# djb_v2_jig.net
KiCad netlist of a schematic drawn in Altium Designer
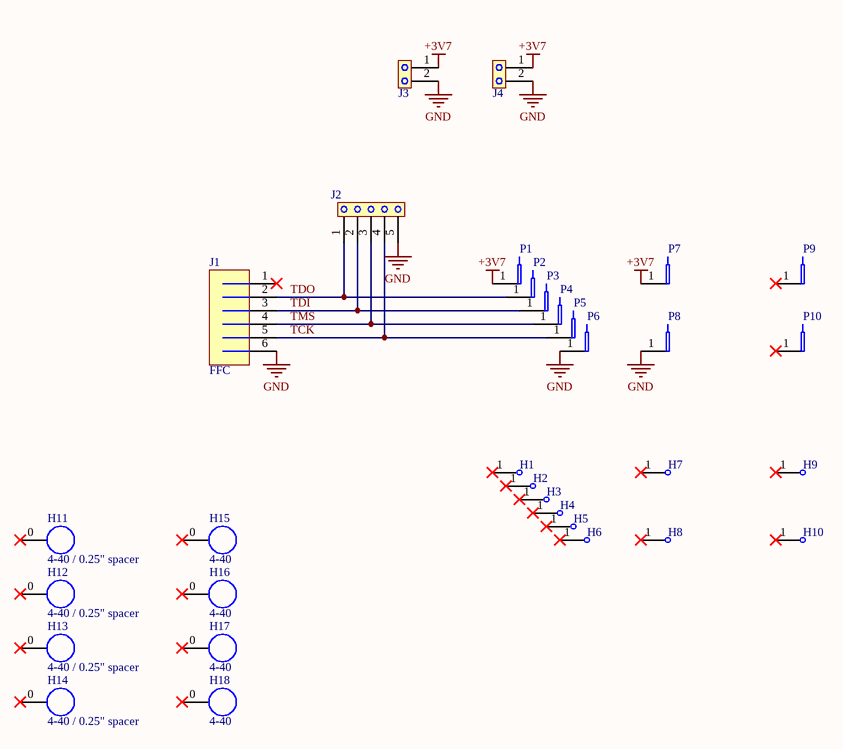
[diagram p0: djb_v2_jig.SchDoc]

(export (version "E")
  (design (tool "Eeschema 10.0.6"))
  (components
    (comp (ref "H1")
      (value "SMITHS_S-00-U-1.3-G_MID")
      (footprint "SMITHS_S-00-U-1.3-G_MID")
      (description "Smiths Interconnect / IDI S-00-U-1.3-G Pogo Pin 0.99mm Centers 16.7mm Long 2.8mm Travel, Mid Mount")
      (libsource (lib "OSP_Symbols") (part "SMITHS_S-00-U-1.3-G_MID"))
    )
    (comp (ref "H2")
      (value "SMITHS_S-00-U-1.3-G_MID")
      (footprint "SMITHS_S-00-U-1.3-G_MID")
      (description "Smiths Interconnect / IDI S-00-U-1.3-G Pogo Pin 0.99mm Centers 16.7mm Long 2.8mm Travel, Mid Mount")
      (libsource (lib "OSP_Symbols") (part "SMITHS_S-00-U-1.3-G_MID"))
    )
    (comp (ref "H3")
      (value "SMITHS_S-00-U-1.3-G_MID")
      (footprint "SMITHS_S-00-U-1.3-G_MID")
      (description "Smiths Interconnect / IDI S-00-U-1.3-G Pogo Pin 0.99mm Centers 16.7mm Long 2.8mm Travel, Mid Mount")
      (libsource (lib "OSP_Symbols") (part "SMITHS_S-00-U-1.3-G_MID"))
    )
    (comp (ref "H4")
      (value "SMITHS_S-00-U-1.3-G_MID")
      (footprint "SMITHS_S-00-U-1.3-G_MID")
      (description "Smiths Interconnect / IDI S-00-U-1.3-G Pogo Pin 0.99mm Centers 16.7mm Long 2.8mm Travel, Mid Mount")
      (libsource (lib "OSP_Symbols") (part "SMITHS_S-00-U-1.3-G_MID"))
    )
    (comp (ref "H5")
      (value "SMITHS_S-00-U-1.3-G_MID")
      (footprint "SMITHS_S-00-U-1.3-G_MID")
      (description "Smiths Interconnect / IDI S-00-U-1.3-G Pogo Pin 0.99mm Centers 16.7mm Long 2.8mm Travel, Mid Mount")
      (libsource (lib "OSP_Symbols") (part "SMITHS_S-00-U-1.3-G_MID"))
    )
    (comp (ref "H6")
      (value "SMITHS_S-00-U-1.3-G_MID")
      (footprint "SMITHS_S-00-U-1.3-G_MID")
      (description "Smiths Interconnect / IDI S-00-U-1.3-G Pogo Pin 0.99mm Centers 16.7mm Long 2.8mm Travel, Mid Mount")
      (libsource (lib "OSP_Symbols") (part "SMITHS_S-00-U-1.3-G_MID"))
    )
    (comp (ref "H7")
      (value "SMITHS_S-00-U-1.3-G_MID")
      (footprint "SMITHS_S-00-U-1.3-G_MID")
      (description "Smiths Interconnect / IDI S-00-U-1.3-G Pogo Pin 0.99mm Centers 16.7mm Long 2.8mm Travel, Mid Mount")
      (libsource (lib "OSP_Symbols") (part "SMITHS_S-00-U-1.3-G_MID"))
    )
    (comp (ref "H8")
      (value "SMITHS_S-00-U-1.3-G_MID")
      (footprint "SMITHS_S-00-U-1.3-G_MID")
      (description "Smiths Interconnect / IDI S-00-U-1.3-G Pogo Pin 0.99mm Centers 16.7mm Long 2.8mm Travel, Mid Mount")
      (libsource (lib "OSP_Symbols") (part "SMITHS_S-00-U-1.3-G_MID"))
    )
    (comp (ref "H9")
      (value "SMITHS_S-00-U-1.3-G_MID")
      (footprint "SMITHS_S-00-U-1.3-G_MID")
      (description "Smiths Interconnect / IDI S-00-U-1.3-G Pogo Pin 0.99mm Centers 16.7mm Long 2.8mm Travel, Mid Mount")
      (libsource (lib "OSP_Symbols") (part "SMITHS_S-00-U-1.3-G_MID"))
    )
    (comp (ref "H10")
      (value "SMITHS_S-00-U-1.3-G_MID")
      (footprint "SMITHS_S-00-U-1.3-G_MID")
      (description "Smiths Interconnect / IDI S-00-U-1.3-G Pogo Pin 0.99mm Centers 16.7mm Long 2.8mm Travel, Mid Mount")
      (libsource (lib "OSP_Symbols") (part "SMITHS_S-00-U-1.3-G_MID"))
    )
    (comp (ref "H11")
      (value "4-40 / 0.25\" spacer")
      (footprint "SCREW_4-40_1/4-SPACER")
      (libsource (lib "OSP_Symbols") (part "SCREW_4-40_1/4-SPACER"))
    )
    (comp (ref "H12")
      (value "4-40 / 0.25\" spacer")
      (footprint "SCREW_4-40_1/4-SPACER")
      (libsource (lib "OSP_Symbols") (part "SCREW_4-40_1/4-SPACER"))
    )
    (comp (ref "H13")
      (value "4-40 / 0.25\" spacer")
      (footprint "SCREW_4-40_1/4-SPACER")
      (libsource (lib "OSP_Symbols") (part "SCREW_4-40_1/4-SPACER"))
    )
    (comp (ref "H14")
      (value "4-40 / 0.25\" spacer")
      (footprint "SCREW_4-40_1/4-SPACER")
      (libsource (lib "OSP_Symbols") (part "SCREW_4-40_1/4-SPACER"))
    )
    (comp (ref "H15")
      (value "4-40")
      (footprint "SCREW_4-40_BLANK")
      (libsource (lib "OSP_Symbols") (part "SCREW_4-40_EMPTY"))
    )
    (comp (ref "H16")
      (value "4-40")
      (footprint "SCREW_4-40_BLANK")
      (libsource (lib "OSP_Symbols") (part "SCREW_4-40_EMPTY"))
    )
    (comp (ref "H17")
      (value "4-40")
      (footprint "SCREW_4-40_BLANK")
      (libsource (lib "OSP_Symbols") (part "SCREW_4-40_EMPTY"))
    )
    (comp (ref "H18")
      (value "4-40")
      (footprint "SCREW_4-40_BLANK")
      (libsource (lib "OSP_Symbols") (part "SCREW_4-40_EMPTY"))
    )
    (comp (ref "J1")
      (value "FFC")
      (footprint "AMPHENOL_HFW6R-1STE1LF")
      (description "Amphenol HFW6R-1STE1LF 6-pin flat flexible cable connector")
      (libsource (lib "OSP_Symbols") (part "AMPHENOL_HFW6R-1STE1LF"))
    )
    (comp (ref "J2")
      (value "HDR_5")
      (footprint "HDR_5")
      (description "5-pin 0.1\" header")
      (libsource (lib "OSP_Symbols") (part "HDR_5"))
    )
    (comp (ref "J3")
      (value "HDR_2")
      (footprint "HDR_2")
      (description "2-pin 0.1\" header")
      (libsource (lib "OSP_Symbols") (part "HDR_2"))
    )
    (comp (ref "J4")
      (value "HDR_2")
      (footprint "HDR_2")
      (description "2-pin 0.1\" header")
      (libsource (lib "OSP_Symbols") (part "HDR_2"))
    )
    (comp (ref "P1")
      (value "SMITHS_S-00-U-1.3-G_TH")
      (footprint "SMITHS_S-00-U-1.3-G_TH")
      (libsource (lib "OSP_Symbols") (part "SMITHS_S-00-U-1.3-G_TH"))
    )
    (comp (ref "P2")
      (value "SMITHS_S-00-U-1.3-G_TH")
      (footprint "SMITHS_S-00-U-1.3-G_TH")
      (libsource (lib "OSP_Symbols") (part "SMITHS_S-00-U-1.3-G_TH"))
    )
    (comp (ref "P3")
      (value "SMITHS_S-00-U-1.3-G_TH")
      (footprint "SMITHS_S-00-U-1.3-G_TH")
      (libsource (lib "OSP_Symbols") (part "SMITHS_S-00-U-1.3-G_TH"))
    )
    (comp (ref "P4")
      (value "SMITHS_S-00-U-1.3-G_TH")
      (footprint "SMITHS_S-00-U-1.3-G_TH")
      (libsource (lib "OSP_Symbols") (part "SMITHS_S-00-U-1.3-G_TH"))
    )
    (comp (ref "P5")
      (value "SMITHS_S-00-U-1.3-G_TH")
      (footprint "SMITHS_S-00-U-1.3-G_TH")
      (libsource (lib "OSP_Symbols") (part "SMITHS_S-00-U-1.3-G_TH"))
    )
    (comp (ref "P6")
      (value "SMITHS_S-00-U-1.3-G_TH")
      (footprint "SMITHS_S-00-U-1.3-G_TH")
      (libsource (lib "OSP_Symbols") (part "SMITHS_S-00-U-1.3-G_TH"))
    )
    (comp (ref "P7")
      (value "SMITHS_S-00-U-1.3-G_TH")
      (footprint "SMITHS_S-00-U-1.3-G_TH")
      (libsource (lib "OSP_Symbols") (part "SMITHS_S-00-U-1.3-G_TH"))
    )
    (comp (ref "P8")
      (value "SMITHS_S-00-U-1.3-G_TH")
      (footprint "SMITHS_S-00-U-1.3-G_TH")
      (libsource (lib "OSP_Symbols") (part "SMITHS_S-00-U-1.3-G_TH"))
    )
    (comp (ref "P9")
      (value "SMITHS_S-00-U-1.3-G_TH")
      (footprint "SMITHS_S-00-U-1.3-G_TH")
      (libsource (lib "OSP_Symbols") (part "SMITHS_S-00-U-1.3-G_TH"))
    )
    (comp (ref "P10")
      (value "SMITHS_S-00-U-1.3-G_TH")
      (footprint "SMITHS_S-00-U-1.3-G_TH")
      (libsource (lib "OSP_Symbols") (part "SMITHS_S-00-U-1.3-G_TH"))
    )
  )
  (nets
    (net (code "1") (name "+3V7") (class "Default")
      (node (ref "J3") (pin "1") (pintype "passive"))
      (node (ref "J4") (pin "1") (pintype "passive"))
      (node (ref "P1") (pin "1") (pinfunction "1_1") (pintype "passive"))
      (node (ref "P7") (pin "1") (pinfunction "1_1") (pintype "passive"))
    )
    (net (code "2") (name "/TCK") (class "Default")
      (node (ref "J1") (pin "5") (pintype "passive"))
      (node (ref "J2") (pin "4") (pintype "passive"))
      (node (ref "P5") (pin "1") (pinfunction "1_1") (pintype "passive"))
    )
    (net (code "3") (name "/TDI") (class "Default")
      (node (ref "J1") (pin "3") (pintype "passive"))
      (node (ref "J2") (pin "2") (pintype "passive"))
      (node (ref "P3") (pin "1") (pinfunction "1_1") (pintype "passive"))
    )
    (net (code "4") (name "/TDO") (class "Default")
      (node (ref "J1") (pin "2") (pintype "passive"))
      (node (ref "J2") (pin "1") (pintype "passive"))
      (node (ref "P2") (pin "1") (pinfunction "1_1") (pintype "passive"))
    )
    (net (code "5") (name "/TMS") (class "Default")
      (node (ref "J1") (pin "4") (pintype "passive"))
      (node (ref "J2") (pin "3") (pintype "passive"))
      (node (ref "P4") (pin "1") (pinfunction "1_1") (pintype "passive"))
    )
    (net (code "6") (name "GND") (class "Default")
      (node (ref "J1") (pin "6") (pintype "passive"))
      (node (ref "J2") (pin "5") (pintype "passive"))
      (node (ref "J3") (pin "2") (pintype "passive"))
      (node (ref "J4") (pin "2") (pintype "passive"))
      (node (ref "P6") (pin "1") (pinfunction "1_1") (pintype "passive"))
      (node (ref "P8") (pin "1") (pinfunction "1_1") (pintype "passive"))
    )
    (net (code "7") (name "unconnected-(H1-Pad1)") (class "Default")
      (node (ref "H1") (pin "1") (pinfunction "1_1") (pintype "passive+no_connect"))
    )
    (net (code "8") (name "unconnected-(H2-Pad1)") (class "Default")
      (node (ref "H2") (pin "1") (pinfunction "1_1") (pintype "passive+no_connect"))
    )
    (net (code "9") (name "unconnected-(H3-Pad1)") (class "Default")
      (node (ref "H3") (pin "1") (pinfunction "1_1") (pintype "passive+no_connect"))
    )
    (net (code "10") (name "unconnected-(H4-Pad1)") (class "Default")
      (node (ref "H4") (pin "1") (pinfunction "1_1") (pintype "passive+no_connect"))
    )
    (net (code "11") (name "unconnected-(H5-Pad1)") (class "Default")
      (node (ref "H5") (pin "1") (pinfunction "1_1") (pintype "passive+no_connect"))
    )
    (net (code "12") (name "unconnected-(H6-Pad1)") (class "Default")
      (node (ref "H6") (pin "1") (pinfunction "1_1") (pintype "passive+no_connect"))
    )
    (net (code "13") (name "unconnected-(H7-Pad1)") (class "Default")
      (node (ref "H7") (pin "1") (pinfunction "1_1") (pintype "passive+no_connect"))
    )
    (net (code "14") (name "unconnected-(H8-Pad1)") (class "Default")
      (node (ref "H8") (pin "1") (pinfunction "1_1") (pintype "passive+no_connect"))
    )
    (net (code "15") (name "unconnected-(H9-Pad1)") (class "Default")
      (node (ref "H9") (pin "1") (pinfunction "1_1") (pintype "passive+no_connect"))
    )
    (net (code "16") (name "unconnected-(H10-Pad1)") (class "Default")
      (node (ref "H10") (pin "1") (pinfunction "1_1") (pintype "passive+no_connect"))
    )
    (net (code "17") (name "unconnected-(H11-Pad0)") (class "Default")
      (node (ref "H11") (pin "0") (pinfunction "0_0") (pintype "passive+no_connect"))
    )
    (net (code "18") (name "unconnected-(H12-Pad0)") (class "Default")
      (node (ref "H12") (pin "0") (pinfunction "0_0") (pintype "passive+no_connect"))
    )
    (net (code "19") (name "unconnected-(H13-Pad0)") (class "Default")
      (node (ref "H13") (pin "0") (pinfunction "0_0") (pintype "passive+no_connect"))
    )
    (net (code "20") (name "unconnected-(H14-Pad0)") (class "Default")
      (node (ref "H14") (pin "0") (pinfunction "0_0") (pintype "passive+no_connect"))
    )
    (net (code "21") (name "unconnected-(H15-Pad0)") (class "Default")
      (node (ref "H15") (pin "0") (pinfunction "0_0") (pintype "passive+no_connect"))
    )
    (net (code "22") (name "unconnected-(H16-Pad0)") (class "Default")
      (node (ref "H16") (pin "0") (pinfunction "0_0") (pintype "passive+no_connect"))
    )
    (net (code "23") (name "unconnected-(H17-Pad0)") (class "Default")
      (node (ref "H17") (pin "0") (pinfunction "0_0") (pintype "passive+no_connect"))
    )
    (net (code "24") (name "unconnected-(H18-Pad0)") (class "Default")
      (node (ref "H18") (pin "0") (pinfunction "0_0") (pintype "passive+no_connect"))
    )
    (net (code "25") (name "unconnected-(J1-Pad1)") (class "Default")
      (node (ref "J1") (pin "1") (pintype "passive+no_connect"))
    )
    (net (code "26") (name "unconnected-(P9-Pad1)") (class "Default")
      (node (ref "P9") (pin "1") (pinfunction "1_1") (pintype "passive+no_connect"))
    )
    (net (code "27") (name "unconnected-(P10-Pad1)") (class "Default")
      (node (ref "P10") (pin "1") (pinfunction "1_1") (pintype "passive+no_connect"))
    )
  )
)
